# Sheet1.net
KiCad netlist of a schematic drawn in Altium Designer
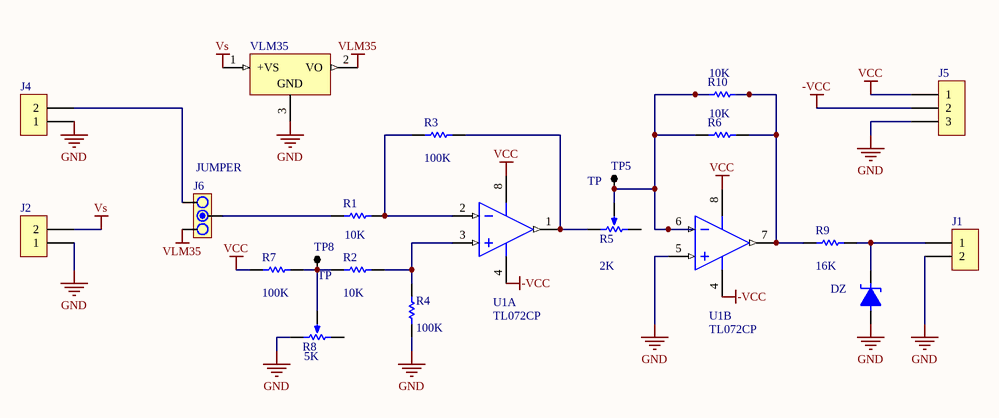
[diagram p0: Sheet1.SchDoc]

(export (version "E")
  (design (tool "Eeschema 10.0.6"))
  (components
    (comp (ref "DZ") (value "~") (footprint "DO41") (libsource (lib "LIBEBAL") (part "DIODO ZENER")))
    (comp (ref "J1") (value "~") (footprint "BORNERA2") (libsource (lib "") (part "BORNERA 2_1")))
    (comp (ref "J2") (value "~") (footprint "BORNERA2") (libsource (lib "LIBEBAL") (part "BORNERA 2")))
    (comp (ref "J4") (value "~") (footprint "BORNERA2") (libsource (lib "LIBEBAL") (part "BORNERA 2")))
    (comp (ref "J5") (value "~") (footprint "BORNERA3") (libsource (lib "LIBEBAL") (part "BORNERA 3")))
    (comp (ref "J6") (value "JUMPER") (footprint "JUMPER3") (libsource (lib "LIBEBAL") (part "JUMPER3")))
    (comp (ref "R1")
      (value "10K")
      (footprint "AXIAL-0.3")
      (description "Resistor")
      (fields (field (name "PUBLISHER") "Altium Limited"))
      (libsource (lib "Miscellaneous Devices") (part "Res1"))
    )
    (comp (ref "R2")
      (value "10K")
      (footprint "AXIAL-0.3")
      (description "Resistor")
      (fields (field (name "PUBLISHER") "Altium Limited"))
      (libsource (lib "Miscellaneous Devices") (part "Res1"))
    )
    (comp (ref "R3")
      (value "100K")
      (footprint "AXIAL-0.3")
      (description "Resistor")
      (fields (field (name "PUBLISHER") "Altium Limited"))
      (libsource (lib "Miscellaneous Devices") (part "Res1"))
    )
    (comp (ref "R4")
      (value "100K")
      (footprint "AXIAL-0.3")
      (description "Resistor")
      (fields (field (name "PUBLISHER") "Altium Limited"))
      (libsource (lib "Miscellaneous Devices") (part "Res1"))
    )
    (comp (ref "R5")
      (value "2K")
      (footprint "VR5")
      (description "Potentiometer")
      (fields (field (name "PUBLISHER") "Altium Limited"))
      (libsource (lib "Miscellaneous Devices") (part "RPot"))
    )
    (comp (ref "R6")
      (value "10K")
      (footprint "AXIAL-0.3")
      (description "Resistor")
      (fields (field (name "PUBLISHER") "Altium Limited"))
      (libsource (lib "Miscellaneous Devices") (part "Res1"))
    )
    (comp (ref "R7")
      (value "100K")
      (footprint "AXIAL-0.3")
      (description "Resistor")
      (fields (field (name "PUBLISHER") "Altium Limited"))
      (libsource (lib "Miscellaneous Devices") (part "Res1"))
    )
    (comp (ref "R8")
      (value "5K")
      (footprint "VR5")
      (description "Potentiometer")
      (fields (field (name "PUBLISHER") "Altium Limited"))
      (libsource (lib "Miscellaneous Devices") (part "RPot"))
    )
    (comp (ref "R9")
      (value "16K")
      (footprint "AXIAL-0.3")
      (description "Resistor")
      (fields (field (name "PUBLISHER") "Altium Limited"))
      (libsource (lib "Miscellaneous Devices") (part "Res1"))
    )
    (comp (ref "R10")
      (value "10K")
      (footprint "AXIAL-0.3")
      (description "Resistor")
      (fields (field (name "PUBLISHER") "Altium Limited"))
      (libsource (lib "Miscellaneous Devices") (part "Res1"))
    )
    (comp (ref "TP5") (value "TP") (footprint "TPTH") (libsource (lib "LIBEBAL") (part "TP")))
    (comp (ref "TP8") (value "TP") (footprint "TPTH") (libsource (lib "LIBEBAL") (part "TP")))
    (comp (ref "U1")
      (value "TL072CP")
      (footprint "TI-P8")
      (fields (field (name "MANUFACTURER") "Texas Instruments"))
      (libsource (lib "TI Amplifiers and Linear Operational Amplifier General Purpose") (part "TL072CP"))
    )
    (comp (ref "VLM35")
      (value "~")
      (footprint "Z03A")
      (description "Precision Centigrade Temperature Sensor, 3-pin TO-92")
      (fields
        (field (name "PARTNUMBER") "LM35CZ")
        (field (name "MANUFACTURER") "National Semiconductor")
        (field (name "PUBLISHER") "Altium Limited")
      )
      (libsource (lib "NSC Temperature Sensor") (part "LM35CZ"))
    )
  )
  (nets
    (net (code "1") (name "-VCC") (class "Default")
      (node (ref "J5") (pin "2") (pinfunction "2_2") (pintype "passive"))
      (node (ref "U1") (pin "4") (pinfunction "VCC-_4") (pintype "power_in"))
    )
    (net (code "2") (name "GND") (class "Default")
      (node (ref "DZ") (pin "1") (pinfunction "1_1") (pintype "passive"))
      (node (ref "J1") (pin "2") (pinfunction "2_2") (pintype "passive"))
      (node (ref "J2") (pin "1") (pinfunction "1_1") (pintype "passive"))
      (node (ref "J4") (pin "1") (pinfunction "1_1") (pintype "passive"))
      (node (ref "J5") (pin "3") (pinfunction "3_3") (pintype "passive"))
      (node (ref "R4") (pin "1") (pinfunction "1_1") (pintype "passive"))
      (node (ref "R8") (pin "2") (pinfunction "BOT_2") (pintype "passive"))
      (node (ref "U1") (pin "5") (pinfunction "IN2+_5") (pintype "input"))
      (node (ref "VLM35") (pin "3") (pinfunction "GND_3") (pintype "power_in"))
    )
    (net (code "3") (name "Net-(DZ-Pad2)") (class "Default")
      (node (ref "DZ") (pin "2") (pinfunction "2_2") (pintype "passive"))
      (node (ref "J1") (pin "1") (pinfunction "1_1") (pintype "passive"))
      (node (ref "R9") (pin "1") (pinfunction "1_1") (pintype "passive"))
    )
    (net (code "4") (name "Net-(J4-Pad2)") (class "Default")
      (node (ref "J4") (pin "2") (pinfunction "2_2") (pintype "passive"))
      (node (ref "J6") (pin "3") (pinfunction "3_3") (pintype "passive"))
    )
    (net (code "5") (name "Net-(J6-Pad2)") (class "Default")
      (node (ref "J6") (pin "2") (pinfunction "2_2") (pintype "passive"))
      (node (ref "R1") (pin "1") (pinfunction "1_1") (pintype "passive"))
    )
    (net (code "6") (name "Net-(R5-BOT)") (class "Default")
      (node (ref "R3") (pin "2") (pinfunction "2_2") (pintype "passive"))
      (node (ref "R5") (pin "2") (pinfunction "BOT_2") (pintype "passive"))
      (node (ref "U1") (pin "1") (pinfunction "OUT1_1") (pintype "output"))
    )
    (net (code "7") (name "Net-(R5-TAP)") (class "Default")
      (node (ref "R10") (pin "1") (pinfunction "1_1") (pintype "passive"))
      (node (ref "R5") (pin "3") (pinfunction "TAP_3") (pintype "passive"))
      (node (ref "R6") (pin "2") (pinfunction "2_2") (pintype "passive"))
      (node (ref "TP5") (pin "1") (pinfunction "1_1") (pintype "passive"))
      (node (ref "U1") (pin "6") (pinfunction "IN2-_6") (pintype "input"))
    )
    (net (code "8") (name "Net-(R8-TAP)") (class "Default")
      (node (ref "R2") (pin "1") (pinfunction "1_1") (pintype "passive"))
      (node (ref "R7") (pin "1") (pinfunction "1_1") (pintype "passive"))
      (node (ref "R8") (pin "3") (pinfunction "TAP_3") (pintype "passive"))
      (node (ref "TP8") (pin "1") (pinfunction "1_1") (pintype "passive"))
    )
    (net (code "9") (name "Net-(U1A-IN1+)") (class "Default")
      (node (ref "R2") (pin "2") (pinfunction "2_2") (pintype "passive"))
      (node (ref "R4") (pin "2") (pinfunction "2_2") (pintype "passive"))
      (node (ref "U1") (pin "3") (pinfunction "IN1+_3") (pintype "input"))
    )
    (net (code "10") (name "Net-(U1A-IN1-)") (class "Default")
      (node (ref "R1") (pin "2") (pinfunction "2_2") (pintype "passive"))
      (node (ref "R3") (pin "1") (pinfunction "1_1") (pintype "passive"))
      (node (ref "U1") (pin "2") (pinfunction "IN1-_2") (pintype "input"))
    )
    (net (code "11") (name "Net-(U1B-OUT2)") (class "Default")
      (node (ref "R10") (pin "2") (pinfunction "2_2") (pintype "passive"))
      (node (ref "R6") (pin "1") (pinfunction "1_1") (pintype "passive"))
      (node (ref "R9") (pin "2") (pinfunction "2_2") (pintype "passive"))
      (node (ref "U1") (pin "7") (pinfunction "OUT2_7") (pintype "output"))
    )
    (net (code "12") (name "VCC") (class "Default")
      (node (ref "J5") (pin "1") (pinfunction "1_1") (pintype "passive"))
      (node (ref "R7") (pin "2") (pinfunction "2_2") (pintype "passive"))
      (node (ref "U1") (pin "8") (pinfunction "VCC+_8") (pintype "power_in"))
    )
    (net (code "13") (name "VLM35") (class "Default")
      (node (ref "J6") (pin "1") (pinfunction "1_1") (pintype "passive"))
      (node (ref "VLM35") (pin "2") (pinfunction "VO_2") (pintype "output"))
    )
    (net (code "14") (name "Vs") (class "Default")
      (node (ref "J2") (pin "2") (pinfunction "2_2") (pintype "passive"))
      (node (ref "VLM35") (pin "1") (pinfunction "+VS_1") (pintype "input"))
    )
    (net (code "15") (name "unconnected-(R5-TOP-Pad1)") (class "Default")
      (node (ref "R5") (pin "1") (pinfunction "TOP_1") (pintype "passive"))
    )
    (net (code "16") (name "unconnected-(R8-TOP-Pad1)") (class "Default")
      (node (ref "R8") (pin "1") (pinfunction "TOP_1") (pintype "passive"))
    )
  )
)
